# Blink_Blink_Beep_Boop.net
KiCad netlist of a schematic drawn in Altium Designer
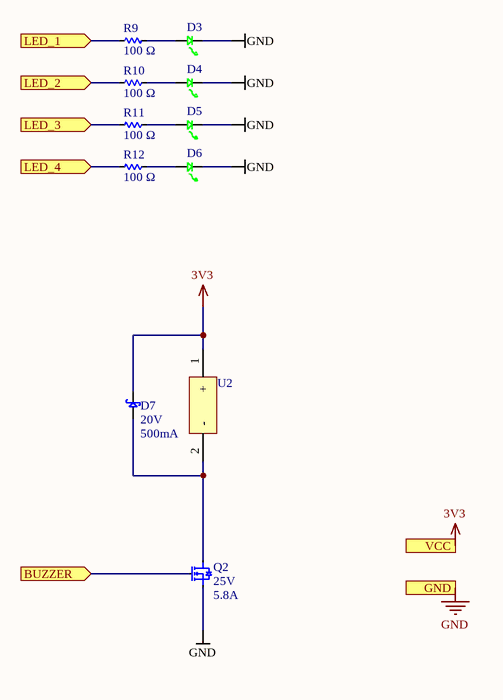
[diagram p0: Blink_Blink_Beep_Boop.SchDoc]

(export (version "E")
  (design (tool "Eeschema 10.0.6"))
  (components
    (comp (ref "D3")
      (value "LED_LY971")
      (footprint "0805_Diode")
      (description "LED 0805 GREEN 20MA")
      (fields
        (field (name "MANUFACTURER") "OSRAM Opto Semiconductors Inc")
        (field (name "MANUFACTURER PART NUMBER") "LG R971-KN-1")
      )
      (libsource (lib "Stanford Student Space Initiative") (part "LED_LY971"))
    )
    (comp (ref "D4")
      (value "LED_LY971")
      (footprint "0805_Diode")
      (description "LED 0805 GREEN 20MA")
      (fields
        (field (name "MANUFACTURER") "OSRAM Opto Semiconductors Inc")
        (field (name "MANUFACTURER PART NUMBER") "LG R971-KN-1")
      )
      (libsource (lib "Stanford Student Space Initiative") (part "LED_LY971"))
    )
    (comp (ref "D5")
      (value "LED_LY971")
      (footprint "0805_Diode")
      (description "LED 0805 GREEN 20MA")
      (fields
        (field (name "MANUFACTURER") "OSRAM Opto Semiconductors Inc")
        (field (name "MANUFACTURER PART NUMBER") "LG R971-KN-1")
      )
      (libsource (lib "Stanford Student Space Initiative") (part "LED_LY971"))
    )
    (comp (ref "D6")
      (value "LED_LY971")
      (footprint "0805_Diode")
      (description "LED 0805 GREEN 20MA")
      (fields
        (field (name "MANUFACTURER") "OSRAM Opto Semiconductors Inc")
        (field (name "MANUFACTURER PART NUMBER") "LG R971-KN-1")
      )
      (libsource (lib "Stanford Student Space Initiative") (part "LED_LY971"))
    )
    (comp (ref "D7")
      (value "Symbol")
      (footprint "SOD123")
      (description "DIODE SCHOTTKY 0.5A 20V SOD-123")
      (fields
        (field (name "MANUFACTURER") "Fairchild Semiconductor")
        (field (name "MANUFACTURER PART NUMBER") "MBR0520L")
        (field (name "VOLTAGE - DC REVERSE (VR) (MAX)") "20V")
        (field (name "CURRENT - AVERAGE RECTIFIED (IO)") "500mA")
      )
      (libsource (lib "") (part "Symbol_1"))
    )
    (comp (ref "Q2")
      (value "Symbol")
      (footprint "3SOT23")
      (description "MOSFET N-CH 25V 5.8A SOT23")
      (fields
        (field (name "MANUFACTURER") "International Rectifier")
        (field (name "MANUFACTURER PART NUMBER") "IRFML8244TRPBF")
        (field (name "DRAIN TO SOURCE VOLTAGE (VDSS)") "25V")
        (field (name "CURRENT - CONTINUOUS DRAIN (ID) @ 25° C") "5.8A")
      )
      (libsource (lib "Stanford Student Space Initiative") (part "Symbol"))
    )
    (comp (ref "R9")
      (value "311-100HRCT-ND")
      (footprint "R0603")
      (description "RES SMD 100 OHM 1% 1/10W 0603")
      (fields
        (field (name "MANUFACTURER PART NUMBER") "RC0603FR-07100RL")
        (field (name "MANUFACTURER") "Yageo")
        (field (name "RESISTANCE") "100 Ω")
      )
      (libsource (lib "Stanford Student Space Initiative") (part "__template_resistor"))
    )
    (comp (ref "R10")
      (value "311-100HRCT-ND")
      (footprint "R0603")
      (description "RES SMD 100 OHM 1% 1/10W 0603")
      (fields
        (field (name "MANUFACTURER PART NUMBER") "RC0603FR-07100RL")
        (field (name "MANUFACTURER") "Yageo")
        (field (name "RESISTANCE") "100 Ω")
      )
      (libsource (lib "Stanford Student Space Initiative") (part "__template_resistor"))
    )
    (comp (ref "R11")
      (value "311-100HRCT-ND")
      (footprint "R0603")
      (description "RES SMD 100 OHM 1% 1/10W 0603")
      (fields
        (field (name "MANUFACTURER PART NUMBER") "RC0603FR-07100RL")
        (field (name "MANUFACTURER") "Yageo")
        (field (name "RESISTANCE") "100 Ω")
      )
      (libsource (lib "Stanford Student Space Initiative") (part "__template_resistor"))
    )
    (comp (ref "R12")
      (value "311-100HRCT-ND")
      (footprint "R0603")
      (description "RES SMD 100 OHM 1% 1/10W 0603")
      (fields
        (field (name "MANUFACTURER PART NUMBER") "RC0603FR-07100RL")
        (field (name "MANUFACTURER") "Yageo")
        (field (name "RESISTANCE") "100 Ω")
      )
      (libsource (lib "Stanford Student Space Initiative") (part "__template_resistor"))
    )
    (comp (ref "U2")
      (value "BUZ_SMT-0540-T-7-R")
      (footprint "BUZ_SMT-0540-T-7-R")
      (description "Peak-Peak Signal Buzzer Single Tone 4kHz Magnetic 2 ~ 4V 78dB @ 3V, 10cm")
      (fields
        (field (name "MANUFACTURER") "PUI Audio, Inc.")
        (field (name "MANUFACTURER PART NUMBER") "SMT-0540-T-7-R")
      )
      (libsource (lib "Stanford Student Space Initiative") (part "BUZ_SMT-0540-T-7-R"))
    )
  )
  (nets
    (net (code "1") (name "/BUZZER") (class "Default") (node (ref "Q2") (pin "1") (pintype "passive")))
    (net (code "2") (name "/LED_1") (class "Default")
      (node (ref "R9") (pin "1") (pinfunction "1_1") (pintype "passive"))
    )
    (net (code "3") (name "/LED_2") (class "Default")
      (node (ref "R10") (pin "1") (pinfunction "1_1") (pintype "passive"))
    )
    (net (code "4") (name "/LED_3") (class "Default")
      (node (ref "R11") (pin "1") (pinfunction "1_1") (pintype "passive"))
    )
    (net (code "5") (name "/LED_4") (class "Default")
      (node (ref "R12") (pin "1") (pinfunction "1_1") (pintype "passive"))
    )
    (net (code "6") (name "3V3") (class "Default")
      (node (ref "D7") (pin "2") (pintype "passive"))
      (node (ref "U2") (pin "1") (pinfunction "+_1") (pintype "passive"))
    )
    (net (code "7") (name "GND") (class "Default")
      (node (ref "D3") (pin "1") (pintype "passive"))
      (node (ref "D4") (pin "1") (pintype "passive"))
      (node (ref "D5") (pin "1") (pintype "passive"))
      (node (ref "D6") (pin "1") (pintype "passive"))
      (node (ref "Q2") (pin "2") (pintype "passive"))
    )
    (net (code "8") (name "Net-(D3-Pad2)") (class "Default")
      (node (ref "D3") (pin "2") (pintype "passive"))
      (node (ref "R9") (pin "2") (pinfunction "2_2") (pintype "passive"))
    )
    (net (code "9") (name "Net-(D4-Pad2)") (class "Default")
      (node (ref "D4") (pin "2") (pintype "passive"))
      (node (ref "R10") (pin "2") (pinfunction "2_2") (pintype "passive"))
    )
    (net (code "10") (name "Net-(D5-Pad2)") (class "Default")
      (node (ref "D5") (pin "2") (pintype "passive"))
      (node (ref "R11") (pin "2") (pinfunction "2_2") (pintype "passive"))
    )
    (net (code "11") (name "Net-(D6-Pad2)") (class "Default")
      (node (ref "D6") (pin "2") (pintype "passive"))
      (node (ref "R12") (pin "2") (pinfunction "2_2") (pintype "passive"))
    )
    (net (code "12") (name "Net-(U2--)") (class "Default")
      (node (ref "D7") (pin "1") (pintype "passive"))
      (node (ref "Q2") (pin "3") (pintype "passive"))
      (node (ref "U2") (pin "2") (pinfunction "-_2") (pintype "passive"))
    )
  )
)
